# Daughterboard.net
KiCad netlist of a schematic drawn in EAGLE
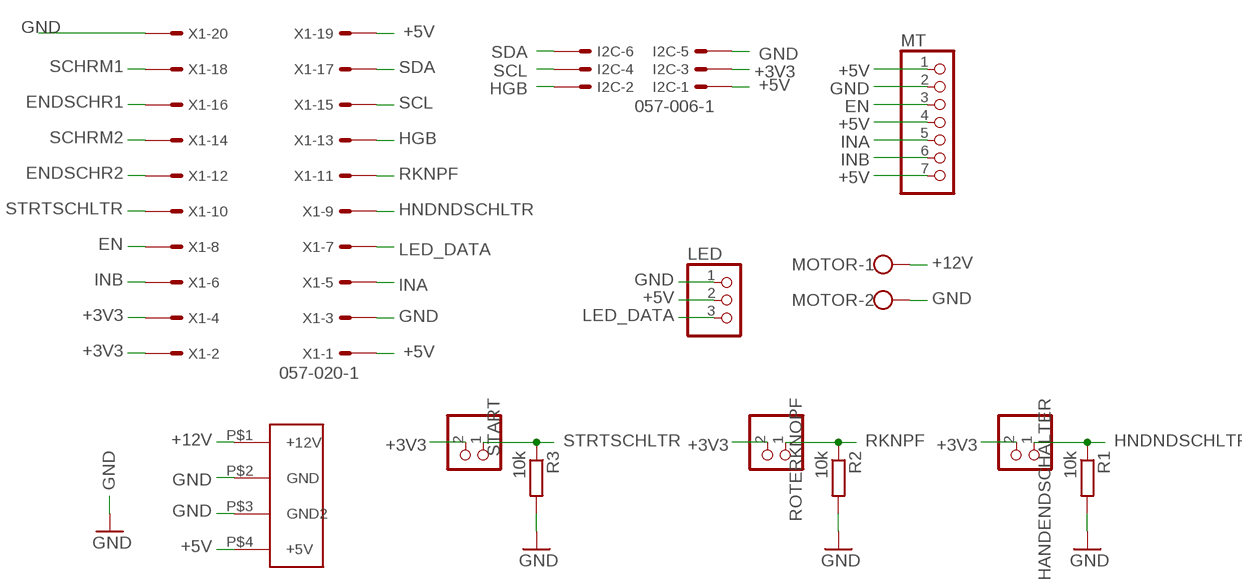
[diagram p0: schematic, sheet 1]

(export (version "E")
  (design (tool "Eeschema 10.0.6"))
  (components
    (comp (ref "HANDENDSCHALTER")
      (value "PINHD-1X2")
      (footprint "eagle-import:1X02")
      (libsource (lib "eagle-import") (part "PINHD-1X2"))
    )
    (comp (ref "I2C")
      (value "057-006-1")
      (footprint "eagle-import:057-006-1")
      (libsource (lib "eagle-import") (part "057-006-1"))
    )
    (comp (ref "LED")
      (value "PINHD-1X3")
      (footprint "eagle-import:1X03")
      (libsource (lib "eagle-import") (part "PINHD-1X3"))
    )
    (comp (ref "MOTOR")
      (value "W237-102")
      (footprint "eagle-import:W237-102")
      (fields (field (name "MPN") "237-102"))
      (libsource (lib "eagle-import") (part "W237-102"))
    )
    (comp (ref "MT")
      (value "PINHD-1X7")
      (footprint "eagle-import:1X07")
      (libsource (lib "eagle-import") (part "PINHD-1X7"))
    )
    (comp (ref "R1")
      (value "10k")
      (footprint "eagle-import:0204_7")
      (libsource (lib "eagle-import") (part "R-EU_0204/7"))
    )
    (comp (ref "R2")
      (value "10k")
      (footprint "eagle-import:0204_7")
      (libsource (lib "eagle-import") (part "R-EU_0204/7"))
    )
    (comp (ref "R3")
      (value "10k")
      (footprint "eagle-import:0204_7")
      (libsource (lib "eagle-import") (part "R-EU_0204/7"))
    )
    (comp (ref "ROTERKNOPF")
      (value "PINHD-1X2")
      (footprint "eagle-import:1X02")
      (libsource (lib "eagle-import") (part "PINHD-1X2"))
    )
    (comp (ref "START")
      (value "PINHD-1X2")
      (footprint "eagle-import:1X02")
      (libsource (lib "eagle-import") (part "PINHD-1X2"))
    )
    (comp (ref "U$1")
      (value "MOLEX_STECKER")
      (footprint "eagle-import:MOLEXCONNECTOR")
      (libsource (lib "eagle-import") (part "MOLEX_STECKER"))
    )
    (comp (ref "X1")
      (value "057-020-1")
      (footprint "eagle-import:057-020-1")
      (libsource (lib "eagle-import") (part "057-020-1"))
    )
  )
  (nets
    (net (code "1") (name "/+3V3") (class "Default")
      (node (ref "HANDENDSCHALTER") (pin "2") (pinfunction "2_2") (pintype "passive"))
      (node (ref "I2C") (pin "3") (pinfunction "S_3") (pintype "passive"))
      (node (ref "ROTERKNOPF") (pin "2") (pinfunction "2_2") (pintype "passive"))
      (node (ref "START") (pin "2") (pinfunction "2_2") (pintype "passive"))
      (node (ref "X1") (pin "2") (pinfunction "S_2") (pintype "passive"))
      (node (ref "X1") (pin "4") (pinfunction "S_4") (pintype "passive"))
    )
    (net (code "2") (name "/+5V") (class "Default")
      (node (ref "I2C") (pin "1") (pinfunction "S_1") (pintype "passive"))
      (node (ref "LED") (pin "2") (pinfunction "2_2") (pintype "passive"))
      (node (ref "MT") (pin "1") (pinfunction "1_1") (pintype "passive"))
      (node (ref "MT") (pin "4") (pinfunction "4_4") (pintype "passive"))
      (node (ref "MT") (pin "7") (pinfunction "7_7") (pintype "passive"))
      (node (ref "U$1") (pin "P$4") (pinfunction "+5V_P$4") (pintype "bidirectional"))
      (node (ref "X1") (pin "1") (pinfunction "S_1") (pintype "passive"))
      (node (ref "X1") (pin "19") (pinfunction "S_19") (pintype "passive"))
    )
    (net (code "3") (name "/+12V") (class "Default")
      (node (ref "MOTOR") (pin "1") (pinfunction "KL_1") (pintype "passive"))
      (node (ref "U$1") (pin "P$1") (pinfunction "+12V_P$1") (pintype "bidirectional"))
    )
    (net (code "4") (name "/EN") (class "Default")
      (node (ref "MT") (pin "3") (pinfunction "3_3") (pintype "passive"))
      (node (ref "X1") (pin "8") (pinfunction "S_8") (pintype "passive"))
    )
    (net (code "5") (name "/ENDSCHR1") (class "Default")
      (node (ref "X1") (pin "16") (pinfunction "S_16") (pintype "passive"))
    )
    (net (code "6") (name "/ENDSCHR2") (class "Default")
      (node (ref "X1") (pin "12") (pinfunction "S_12") (pintype "passive"))
    )
    (net (code "7") (name "/HGB") (class "Default")
      (node (ref "I2C") (pin "2") (pinfunction "S_2") (pintype "passive"))
      (node (ref "X1") (pin "13") (pinfunction "S_13") (pintype "passive"))
    )
    (net (code "8") (name "/HNDNDSCHLTR") (class "Default")
      (node (ref "HANDENDSCHALTER") (pin "1") (pinfunction "1_1") (pintype "passive"))
      (node (ref "R1") (pin "1") (pinfunction "1_1") (pintype "passive"))
      (node (ref "X1") (pin "9") (pinfunction "S_9") (pintype "passive"))
    )
    (net (code "9") (name "/INA") (class "Default")
      (node (ref "MT") (pin "5") (pinfunction "5_5") (pintype "passive"))
      (node (ref "X1") (pin "5") (pinfunction "S_5") (pintype "passive"))
    )
    (net (code "10") (name "/INB") (class "Default")
      (node (ref "MT") (pin "6") (pinfunction "6_6") (pintype "passive"))
      (node (ref "X1") (pin "6") (pinfunction "S_6") (pintype "passive"))
    )
    (net (code "11") (name "/LED_DATA") (class "Default")
      (node (ref "LED") (pin "3") (pinfunction "3_3") (pintype "passive"))
      (node (ref "X1") (pin "7") (pinfunction "S_7") (pintype "passive"))
    )
    (net (code "12") (name "/RKNPF") (class "Default")
      (node (ref "R2") (pin "1") (pinfunction "1_1") (pintype "passive"))
      (node (ref "ROTERKNOPF") (pin "1") (pinfunction "1_1") (pintype "passive"))
      (node (ref "X1") (pin "11") (pinfunction "S_11") (pintype "passive"))
    )
    (net (code "13") (name "/SCHRM1") (class "Default")
      (node (ref "X1") (pin "18") (pinfunction "S_18") (pintype "passive"))
    )
    (net (code "14") (name "/SCHRM2") (class "Default")
      (node (ref "X1") (pin "14") (pinfunction "S_14") (pintype "passive"))
    )
    (net (code "15") (name "/SCL") (class "Default")
      (node (ref "I2C") (pin "4") (pinfunction "S_4") (pintype "passive"))
      (node (ref "X1") (pin "15") (pinfunction "S_15") (pintype "passive"))
    )
    (net (code "16") (name "/SDA") (class "Default")
      (node (ref "I2C") (pin "6") (pinfunction "S_6") (pintype "passive"))
      (node (ref "X1") (pin "17") (pinfunction "S_17") (pintype "passive"))
    )
    (net (code "17") (name "/STRTSCHLTR") (class "Default")
      (node (ref "R3") (pin "1") (pinfunction "1_1") (pintype "passive"))
      (node (ref "START") (pin "1") (pinfunction "1_1") (pintype "passive"))
      (node (ref "X1") (pin "10") (pinfunction "S_10") (pintype "passive"))
    )
    (net (code "18") (name "GND") (class "Default")
      (node (ref "I2C") (pin "5") (pinfunction "S_5") (pintype "passive"))
      (node (ref "LED") (pin "1") (pinfunction "1_1") (pintype "passive"))
      (node (ref "MOTOR") (pin "2") (pinfunction "KL_2") (pintype "passive"))
      (node (ref "MT") (pin "2") (pinfunction "2_2") (pintype "passive"))
      (node (ref "R1") (pin "2") (pinfunction "2_2") (pintype "passive"))
      (node (ref "R2") (pin "2") (pinfunction "2_2") (pintype "passive"))
      (node (ref "R3") (pin "2") (pinfunction "2_2") (pintype "passive"))
      (node (ref "U$1") (pin "P$2") (pinfunction "GND_P$2") (pintype "bidirectional"))
      (node (ref "U$1") (pin "P$3") (pinfunction "GND2_P$3") (pintype "bidirectional"))
      (node (ref "X1") (pin "20") (pinfunction "S_20") (pintype "passive"))
      (node (ref "X1") (pin "3") (pinfunction "S_3") (pintype "passive"))
    )
  )
)
